# MSP432.net
KiCad netlist of a schematic drawn in Altium Designer
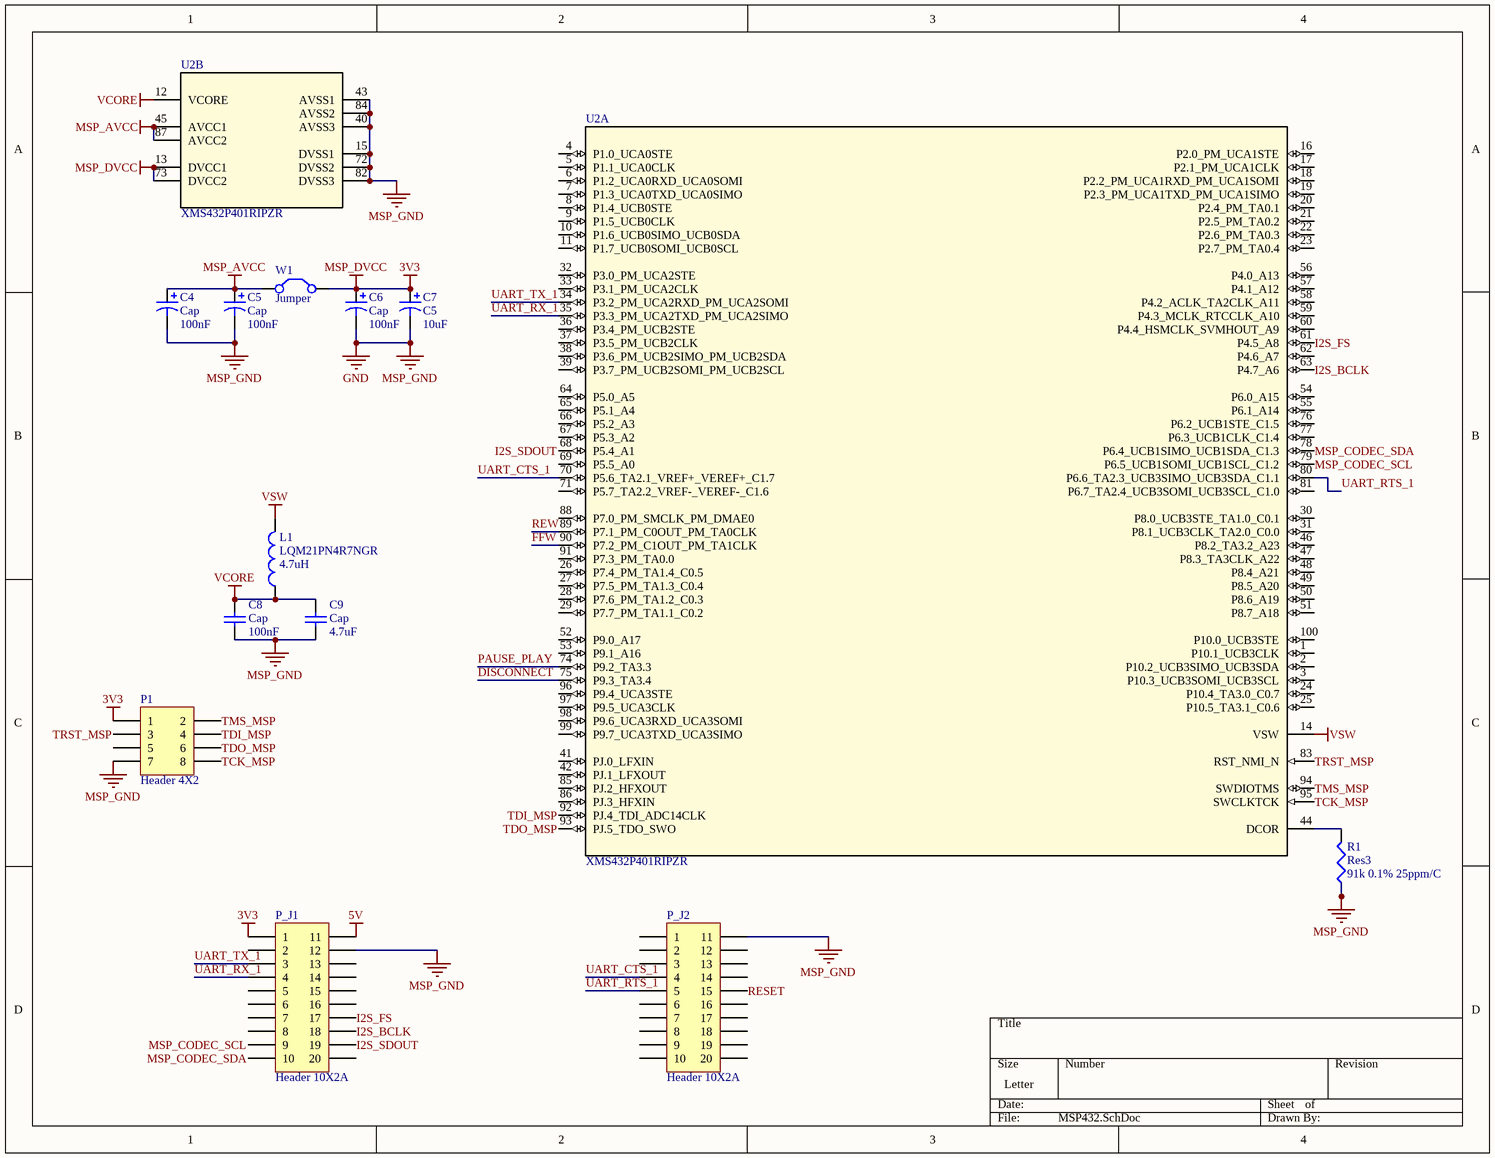
[diagram p0: MSP432.SchDoc]

(export (version "E")
  (design (tool "Eeschema 10.0.6"))
  (components
    (comp (ref "C4")
      (value "Cap")
      (footprint "C0805")
      (description "Polarized Capacitor (Surface Mount)")
      (fields (field (name "ALTIUM_VALUE") "100nF") (field (name "PUBLISHER") "Altium Limited"))
      (libsource (lib "Miscellaneous Devices") (part "Cap Pol3"))
    )
    (comp (ref "C5")
      (value "Cap")
      (footprint "C0805")
      (description "Polarized Capacitor (Surface Mount)")
      (fields (field (name "ALTIUM_VALUE") "100nF") (field (name "PUBLISHER") "Altium Limited"))
      (libsource (lib "Miscellaneous Devices") (part "Cap Pol3"))
    )
    (comp (ref "C6")
      (value "Cap")
      (footprint "C0805")
      (description "Polarized Capacitor (Surface Mount)")
      (fields (field (name "ALTIUM_VALUE") "100nF") (field (name "PUBLISHER") "Altium Limited"))
      (libsource (lib "Miscellaneous Devices") (part "Cap Pol3"))
    )
    (comp (ref "C7")
      (value "C5")
      (footprint "C0805")
      (description "Polarized Capacitor (Surface Mount)")
      (fields (field (name "ALTIUM_VALUE") "10uF") (field (name "PUBLISHER") "Altium Limited"))
      (libsource (lib "Miscellaneous Devices") (part "Cap Pol3"))
    )
    (comp (ref "C8")
      (value "Cap")
      (footprint "C0805")
      (description "Capacitor (Semiconductor SIM Model)")
      (fields (field (name "ALTIUM_VALUE") "100nF") (field (name "PUBLISHER") "Altium Limited"))
      (libsource (lib "Miscellaneous Devices") (part "Cap Semi"))
    )
    (comp (ref "C9")
      (value "Cap")
      (footprint "C0805")
      (description "Capacitor (Semiconductor SIM Model)")
      (fields (field (name "ALTIUM_VALUE") "4.7uF") (field (name "PUBLISHER") "Altium Limited"))
      (libsource (lib "Miscellaneous Devices") (part "Cap Semi"))
    )
    (comp (ref "L1")
      (value "LQM21PN4R7NGR")
      (footprint "6-0805_N")
      (description "Inductor")
      (fields (field (name "ALTIUM_VALUE") "4.7uH") (field (name "PUBLISHER") "Altium Limited"))
      (libsource (lib "Miscellaneous Devices") (part "Inductor"))
    )
    (comp (ref "P1")
      (value "Header 4X2")
      (footprint "HDR2X4")
      (description "Header, 4-Pin, Dual row")
      (fields (field (name "PUBLISHER") "Altium Limited"))
      (libsource (lib "Miscellaneous Connectors") (part "Header 4X2"))
    )
    (comp (ref "P_J1")
      (value "Header 10X2A")
      (footprint "HDR2X10_CEN")
      (description "Header, 10-Pin, Dual row")
      (fields (field (name "PUBLISHER") "Altium Limited"))
      (libsource (lib "Miscellaneous Connectors") (part "Header 10X2A"))
    )
    (comp (ref "P_J2")
      (value "Header 10X2A")
      (footprint "HDR2X10_CEN")
      (description "Header, 10-Pin, Dual row")
      (fields (field (name "PUBLISHER") "Altium Limited"))
      (libsource (lib "Miscellaneous Connectors") (part "Header 10X2A"))
    )
    (comp (ref "R1")
      (value "Res3")
      (footprint "14-1210")
      (description "Resistor")
      (fields (field (name "ALTIUM_VALUE") "91k 0.1% 25ppm/C") (field (name "PUBLISHER") "Altium Limited"))
      (libsource (lib "Miscellaneous Devices") (part "Res3"))
    )
    (comp (ref "U2")
      (value "XMS432P401RIPZR")
      (footprint "PZ0100A_N")
      (description "Imported")
      (fields (field (name "MANUFACTURER") "Texas Instruments"))
      (libsource (lib "XMS432P401R") (part "XMS432P401RIPZR"))
    )
    (comp (ref "W1")
      (value "Jumper")
      (footprint "RAD-0.2")
      (description "Jumper Wire")
      (fields (field (name "PUBLISHER") "Altium Limited"))
      (libsource (lib "Miscellaneous Devices") (part "Jumper"))
    )
  )
  (nets
    (net (code "1") (name "/DISCONNECT") (class "Default")
      (node (ref "U2") (pin "75") (pinfunction "P9.3_TA3.4_75") (pintype "bidirectional"))
    )
    (net (code "2") (name "/FFW") (class "Default")
      (node (ref "U2") (pin "90") (pinfunction "P7.2_PM_C1OUT_PM_TA1CLK_90") (pintype "bidirectional"))
    )
    (net (code "3") (name "/I2S_BCLK") (class "Default")
      (node (ref "P_J1") (pin "18") (pinfunction "18_18") (pintype "passive"))
      (node (ref "U2") (pin "63") (pinfunction "P4.7_A6_63") (pintype "bidirectional"))
    )
    (net (code "4") (name "/I2S_FS") (class "Default")
      (node (ref "P_J1") (pin "17") (pinfunction "17_17") (pintype "passive"))
      (node (ref "U2") (pin "61") (pinfunction "P4.5_A8_61") (pintype "bidirectional"))
    )
    (net (code "5") (name "/I2S_SDOUT") (class "Default")
      (node (ref "P_J1") (pin "19") (pinfunction "19_19") (pintype "passive"))
      (node (ref "U2") (pin "68") (pinfunction "P5.4_A1_68") (pintype "bidirectional"))
    )
    (net (code "6") (name "/MSP_CODEC_SCL") (class "Default")
      (node (ref "P_J1") (pin "9") (pinfunction "9_9") (pintype "passive"))
      (node (ref "U2") (pin "79") (pinfunction "P6.5_UCB1SOMI_UCB1SCL_C1.2_79") (pintype "bidirectional"))
    )
    (net (code "7") (name "/MSP_CODEC_SDA") (class "Default")
      (node (ref "P_J1") (pin "10") (pinfunction "10_10") (pintype "passive"))
      (node (ref "U2") (pin "78") (pinfunction "P6.4_UCB1SIMO_UCB1SDA_C1.3_78") (pintype "bidirectional"))
    )
    (net (code "8") (name "/PAUSE_PLAY") (class "Default")
      (node (ref "U2") (pin "74") (pinfunction "P9.2_TA3.3_74") (pintype "bidirectional"))
    )
    (net (code "9") (name "/RESET") (class "Default")
      (node (ref "P_J2") (pin "15") (pinfunction "15_15") (pintype "passive"))
    )
    (net (code "10") (name "/REW") (class "Default")
      (node (ref "U2") (pin "89") (pinfunction "P7.1_PM_C0OUT_PM_TA0CLK_89") (pintype "bidirectional"))
    )
    (net (code "11") (name "/TCK_MSP") (class "Default")
      (node (ref "P1") (pin "8") (pinfunction "8_8") (pintype "passive"))
      (node (ref "U2") (pin "95") (pinfunction "SWCLKTCK_95") (pintype "input"))
    )
    (net (code "12") (name "/TDI_MSP") (class "Default")
      (node (ref "P1") (pin "4") (pinfunction "4_4") (pintype "passive"))
      (node (ref "U2") (pin "92") (pinfunction "PJ.4_TDI_ADC14CLK_92") (pintype "bidirectional"))
    )
    (net (code "13") (name "/TDO_MSP") (class "Default")
      (node (ref "P1") (pin "6") (pinfunction "6_6") (pintype "passive"))
      (node (ref "U2") (pin "93") (pinfunction "PJ.5_TDO_SWO_93") (pintype "bidirectional"))
    )
    (net (code "14") (name "/TMS_MSP") (class "Default")
      (node (ref "P1") (pin "2") (pinfunction "2_2") (pintype "passive"))
      (node (ref "U2") (pin "94") (pinfunction "SWDIOTMS_94") (pintype "bidirectional"))
    )
    (net (code "15") (name "/TRST_MSP") (class "Default")
      (node (ref "P1") (pin "3") (pinfunction "3_3") (pintype "passive"))
      (node (ref "U2") (pin "83") (pinfunction "RST_NMI_N_83") (pintype "input"))
    )
    (net (code "16") (name "/UART_CTS_1") (class "Default")
      (node (ref "P_J2") (pin "4") (pinfunction "4_4") (pintype "passive"))
      (node (ref "U2") (pin "70") (pinfunction "P5.6_TA2.1_VREF+_VEREF+_C1.7_70") (pintype "bidirectional"))
    )
    (net (code "17") (name "/UART_RTS_1") (class "Default")
      (node (ref "P_J2") (pin "5") (pinfunction "5_5") (pintype "passive"))
      (node (ref "U2") (pin "80") (pinfunction "P6.6_TA2.3_UCB3SIMO_UCB3SDA_C1.1_80") (pintype "bidirectional"))
    )
    (net (code "18") (name "/UART_RX_1") (class "Default")
      (node (ref "P_J1") (pin "4") (pinfunction "4_4") (pintype "passive"))
      (node (ref "U2") (pin "35") (pinfunction "P3.3_PM_UCA2TXD_PM_UCA2SIMO_35") (pintype "bidirectional"))
    )
    (net (code "19") (name "/UART_TX_1") (class "Default")
      (node (ref "P_J1") (pin "3") (pinfunction "3_3") (pintype "passive"))
      (node (ref "U2") (pin "34") (pinfunction "P3.2_PM_UCA2RXD_PM_UCA2SOMI_34") (pintype "bidirectional"))
    )
    (net (code "20") (name "3V3") (class "Default")
      (node (ref "C6") (pin "1") (pinfunction "1_1") (pintype "passive"))
      (node (ref "C7") (pin "1") (pinfunction "1_1") (pintype "passive"))
      (node (ref "P1") (pin "1") (pinfunction "1_1") (pintype "passive"))
      (node (ref "P_J1") (pin "1") (pinfunction "1_1") (pintype "passive"))
      (node (ref "U2") (pin "13") (pinfunction "DVCC1_13") (pintype "power_in"))
      (node (ref "U2") (pin "73") (pinfunction "DVCC2_73") (pintype "power_in"))
      (node (ref "W1") (pin "2") (pinfunction "C2_2") (pintype "passive"))
    )
    (net (code "21") (name "5V") (class "Default")
      (node (ref "P_J1") (pin "11") (pinfunction "11_11") (pintype "passive"))
    )
    (net (code "22") (name "GND") (class "Default")
      (node (ref "C4") (pin "2") (pinfunction "2_2") (pintype "passive"))
      (node (ref "C5") (pin "2") (pinfunction "2_2") (pintype "passive"))
      (node (ref "C6") (pin "2") (pinfunction "2_2") (pintype "passive"))
      (node (ref "C7") (pin "2") (pinfunction "2_2") (pintype "passive"))
      (node (ref "C8") (pin "1") (pinfunction "1_1") (pintype "passive"))
      (node (ref "C9") (pin "2") (pinfunction "2_2") (pintype "passive"))
      (node (ref "P1") (pin "7") (pinfunction "7_7") (pintype "passive"))
      (node (ref "P_J1") (pin "12") (pinfunction "12_12") (pintype "passive"))
      (node (ref "P_J2") (pin "11") (pinfunction "11_11") (pintype "passive"))
      (node (ref "R1") (pin "1") (pinfunction "1_1") (pintype "passive"))
      (node (ref "U2") (pin "15") (pinfunction "DVSS1_15") (pintype "power_in"))
      (node (ref "U2") (pin "40") (pinfunction "AVSS3_40") (pintype "power_in"))
      (node (ref "U2") (pin "43") (pinfunction "AVSS1_43") (pintype "power_in"))
      (node (ref "U2") (pin "72") (pinfunction "DVSS2_72") (pintype "power_in"))
      (node (ref "U2") (pin "82") (pinfunction "DVSS3_82") (pintype "power_in"))
      (node (ref "U2") (pin "84") (pinfunction "AVSS2_84") (pintype "power_in"))
    )
    (net (code "23") (name "MSP_AVCC") (class "Default")
      (node (ref "C4") (pin "1") (pinfunction "1_1") (pintype "passive"))
      (node (ref "C5") (pin "1") (pinfunction "1_1") (pintype "passive"))
      (node (ref "U2") (pin "45") (pinfunction "AVCC1_45") (pintype "power_in"))
      (node (ref "U2") (pin "87") (pinfunction "AVCC2_87") (pintype "power_in"))
      (node (ref "W1") (pin "1") (pinfunction "C1_1") (pintype "passive"))
    )
    (net (code "24") (name "Net-(U2A-DCOR)") (class "Default")
      (node (ref "R1") (pin "2") (pinfunction "2_2") (pintype "passive"))
      (node (ref "U2") (pin "44") (pinfunction "DCOR_44") (pintype "passive"))
    )
    (net (code "25") (name "VCORE") (class "Default")
      (node (ref "C8") (pin "2") (pinfunction "2_2") (pintype "passive"))
      (node (ref "C9") (pin "1") (pinfunction "1_1") (pintype "passive"))
      (node (ref "L1") (pin "1") (pinfunction "1_1") (pintype "passive"))
      (node (ref "U2") (pin "12") (pinfunction "VCORE_12") (pintype "power_in"))
    )
    (net (code "26") (name "VSW") (class "Default")
      (node (ref "L1") (pin "2") (pinfunction "2_2") (pintype "passive"))
      (node (ref "U2") (pin "14") (pinfunction "VSW_14") (pintype "passive"))
    )
    (net (code "27") (name "unconnected-(P1-Pad5)") (class "Default")
      (node (ref "P1") (pin "5") (pinfunction "5_5") (pintype "passive"))
    )
    (net (code "28") (name "unconnected-(P_J1-Pad2)") (class "Default")
      (node (ref "P_J1") (pin "2") (pinfunction "2_2") (pintype "passive"))
    )
    (net (code "29") (name "unconnected-(P_J1-Pad5)") (class "Default")
      (node (ref "P_J1") (pin "5") (pinfunction "5_5") (pintype "passive"))
    )
    (net (code "30") (name "unconnected-(P_J1-Pad6)") (class "Default")
      (node (ref "P_J1") (pin "6") (pinfunction "6_6") (pintype "passive"))
    )
    (net (code "31") (name "unconnected-(P_J1-Pad7)") (class "Default")
      (node (ref "P_J1") (pin "7") (pinfunction "7_7") (pintype "passive"))
    )
    (net (code "32") (name "unconnected-(P_J1-Pad8)") (class "Default")
      (node (ref "P_J1") (pin "8") (pinfunction "8_8") (pintype "passive"))
    )
    (net (code "33") (name "unconnected-(P_J1-Pad13)") (class "Default")
      (node (ref "P_J1") (pin "13") (pinfunction "13_13") (pintype "passive"))
    )
    (net (code "34") (name "unconnected-(P_J1-Pad14)") (class "Default")
      (node (ref "P_J1") (pin "14") (pinfunction "14_14") (pintype "passive"))
    )
    (net (code "35") (name "unconnected-(P_J1-Pad15)") (class "Default")
      (node (ref "P_J1") (pin "15") (pinfunction "15_15") (pintype "passive"))
    )
    (net (code "36") (name "unconnected-(P_J1-Pad16)") (class "Default")
      (node (ref "P_J1") (pin "16") (pinfunction "16_16") (pintype "passive"))
    )
    (net (code "37") (name "unconnected-(P_J1-Pad20)") (class "Default")
      (node (ref "P_J1") (pin "20") (pinfunction "20_20") (pintype "passive"))
    )
    (net (code "38") (name "unconnected-(P_J2-Pad1)") (class "Default")
      (node (ref "P_J2") (pin "1") (pinfunction "1_1") (pintype "passive"))
    )
    (net (code "39") (name "unconnected-(P_J2-Pad2)") (class "Default")
      (node (ref "P_J2") (pin "2") (pinfunction "2_2") (pintype "passive"))
    )
    (net (code "40") (name "unconnected-(P_J2-Pad3)") (class "Default")
      (node (ref "P_J2") (pin "3") (pinfunction "3_3") (pintype "passive"))
    )
    (net (code "41") (name "unconnected-(P_J2-Pad6)") (class "Default")
      (node (ref "P_J2") (pin "6") (pinfunction "6_6") (pintype "passive"))
    )
    (net (code "42") (name "unconnected-(P_J2-Pad7)") (class "Default")
      (node (ref "P_J2") (pin "7") (pinfunction "7_7") (pintype "passive"))
    )
    (net (code "43") (name "unconnected-(P_J2-Pad8)") (class "Default")
      (node (ref "P_J2") (pin "8") (pinfunction "8_8") (pintype "passive"))
    )
    (net (code "44") (name "unconnected-(P_J2-Pad9)") (class "Default")
      (node (ref "P_J2") (pin "9") (pinfunction "9_9") (pintype "passive"))
    )
    (net (code "45") (name "unconnected-(P_J2-Pad10)") (class "Default")
      (node (ref "P_J2") (pin "10") (pinfunction "10_10") (pintype "passive"))
    )
    (net (code "46") (name "unconnected-(P_J2-Pad12)") (class "Default")
      (node (ref "P_J2") (pin "12") (pinfunction "12_12") (pintype "passive"))
    )
    (net (code "47") (name "unconnected-(P_J2-Pad13)") (class "Default")
      (node (ref "P_J2") (pin "13") (pinfunction "13_13") (pintype "passive"))
    )
    (net (code "48") (name "unconnected-(P_J2-Pad14)") (class "Default")
      (node (ref "P_J2") (pin "14") (pinfunction "14_14") (pintype "passive"))
    )
    (net (code "49") (name "unconnected-(P_J2-Pad16)") (class "Default")
      (node (ref "P_J2") (pin "16") (pinfunction "16_16") (pintype "passive"))
    )
    (net (code "50") (name "unconnected-(P_J2-Pad17)") (class "Default")
      (node (ref "P_J2") (pin "17") (pinfunction "17_17") (pintype "passive"))
    )
    (net (code "51") (name "unconnected-(P_J2-Pad18)") (class "Default")
      (node (ref "P_J2") (pin "18") (pinfunction "18_18") (pintype "passive"))
    )
    (net (code "52") (name "unconnected-(P_J2-Pad19)") (class "Default")
      (node (ref "P_J2") (pin "19") (pinfunction "19_19") (pintype "passive"))
    )
    (net (code "53") (name "unconnected-(P_J2-Pad20)") (class "Default")
      (node (ref "P_J2") (pin "20") (pinfunction "20_20") (pintype "passive"))
    )
    (net (code "54") (name "unconnected-(U2A-P1.0_UCA0STE-Pad4)") (class "Default")
      (node (ref "U2") (pin "4") (pinfunction "P1.0_UCA0STE_4") (pintype "bidirectional"))
    )
    (net (code "55") (name "unconnected-(U2A-P1.1_UCA0CLK-Pad5)") (class "Default")
      (node (ref "U2") (pin "5") (pinfunction "P1.1_UCA0CLK_5") (pintype "bidirectional"))
    )
    (net (code "56") (name "unconnected-(U2A-P1.2_UCA0RXD_UCA0SOMI-Pad6)") (class "Default")
      (node (ref "U2") (pin "6") (pinfunction "P1.2_UCA0RXD_UCA0SOMI_6") (pintype "bidirectional"))
    )
    (net (code "57") (name "unconnected-(U2A-P1.3_UCA0TXD_UCA0SIMO-Pad7)") (class "Default")
      (node (ref "U2") (pin "7") (pinfunction "P1.3_UCA0TXD_UCA0SIMO_7") (pintype "bidirectional"))
    )
    (net (code "58") (name "unconnected-(U2A-P1.4_UCB0STE-Pad8)") (class "Default")
      (node (ref "U2") (pin "8") (pinfunction "P1.4_UCB0STE_8") (pintype "bidirectional"))
    )
    (net (code "59") (name "unconnected-(U2A-P1.5_UCB0CLK-Pad9)") (class "Default")
      (node (ref "U2") (pin "9") (pinfunction "P1.5_UCB0CLK_9") (pintype "bidirectional"))
    )
    (net (code "60") (name "unconnected-(U2A-P1.6_UCB0SIMO_UCB0SDA-Pad10)") (class "Default")
      (node (ref "U2") (pin "10") (pinfunction "P1.6_UCB0SIMO_UCB0SDA_10") (pintype "bidirectional"))
    )
    (net (code "61") (name "unconnected-(U2A-P1.7_UCB0SOMI_UCB0SCL-Pad11)") (class "Default")
      (node (ref "U2") (pin "11") (pinfunction "P1.7_UCB0SOMI_UCB0SCL_11") (pintype "bidirectional"))
    )
    (net (code "62") (name "unconnected-(U2A-P2.0_PM_UCA1STE-Pad16)") (class "Default")
      (node (ref "U2") (pin "16") (pinfunction "P2.0_PM_UCA1STE_16") (pintype "bidirectional"))
    )
    (net (code "63") (name "unconnected-(U2A-P2.1_PM_UCA1CLK-Pad17)") (class "Default")
      (node (ref "U2") (pin "17") (pinfunction "P2.1_PM_UCA1CLK_17") (pintype "bidirectional"))
    )
    (net (code "64") (name "unconnected-(U2A-P2.2_PM_UCA1RXD_PM_UCA1SOMI-Pad18)") (class "Default")
      (node (ref "U2") (pin "18") (pinfunction "P2.2_PM_UCA1RXD_PM_UCA1SOMI_18") (pintype "bidirectional"))
    )
    (net (code "65") (name "unconnected-(U2A-P2.3_PM_UCA1TXD_PM_UCA1SIMO-Pad19)") (class "Default")
      (node (ref "U2") (pin "19") (pinfunction "P2.3_PM_UCA1TXD_PM_UCA1SIMO_19") (pintype "bidirectional"))
    )
    (net (code "66") (name "unconnected-(U2A-P2.4_PM_TA0.1-Pad20)") (class "Default")
      (node (ref "U2") (pin "20") (pinfunction "P2.4_PM_TA0.1_20") (pintype "bidirectional"))
    )
    (net (code "67") (name "unconnected-(U2A-P2.5_PM_TA0.2-Pad21)") (class "Default")
      (node (ref "U2") (pin "21") (pinfunction "P2.5_PM_TA0.2_21") (pintype "bidirectional"))
    )
    (net (code "68") (name "unconnected-(U2A-P2.6_PM_TA0.3-Pad22)") (class "Default")
      (node (ref "U2") (pin "22") (pinfunction "P2.6_PM_TA0.3_22") (pintype "bidirectional"))
    )
    (net (code "69") (name "unconnected-(U2A-P2.7_PM_TA0.4-Pad23)") (class "Default")
      (node (ref "U2") (pin "23") (pinfunction "P2.7_PM_TA0.4_23") (pintype "bidirectional"))
    )
    (net (code "70") (name "unconnected-(U2A-P3.0_PM_UCA2STE-Pad32)") (class "Default")
      (node (ref "U2") (pin "32") (pinfunction "P3.0_PM_UCA2STE_32") (pintype "bidirectional"))
    )
    (net (code "71") (name "unconnected-(U2A-P3.1_PM_UCA2CLK-Pad33)") (class "Default")
      (node (ref "U2") (pin "33") (pinfunction "P3.1_PM_UCA2CLK_33") (pintype "bidirectional"))
    )
    (net (code "72") (name "unconnected-(U2A-P3.4_PM_UCB2STE-Pad36)") (class "Default")
      (node (ref "U2") (pin "36") (pinfunction "P3.4_PM_UCB2STE_36") (pintype "bidirectional"))
    )
    (net (code "73") (name "unconnected-(U2A-P3.5_PM_UCB2CLK-Pad37)") (class "Default")
      (node (ref "U2") (pin "37") (pinfunction "P3.5_PM_UCB2CLK_37") (pintype "bidirectional"))
    )
    (net (code "74") (name "unconnected-(U2A-P3.6_PM_UCB2SIMO_PM_UCB2SDA-Pad38)") (class "Default")
      (node (ref "U2") (pin "38") (pinfunction "P3.6_PM_UCB2SIMO_PM_UCB2SDA_38") (pintype "bidirectional"))
    )
    (net (code "75") (name "unconnected-(U2A-P3.7_PM_UCB2SOMI_PM_UCB2SCL-Pad39)") (class "Default")
      (node (ref "U2") (pin "39") (pinfunction "P3.7_PM_UCB2SOMI_PM_UCB2SCL_39") (pintype "bidirectional"))
    )
    (net (code "76") (name "unconnected-(U2A-P4.0_A13-Pad56)") (class "Default")
      (node (ref "U2") (pin "56") (pinfunction "P4.0_A13_56") (pintype "bidirectional"))
    )
    (net (code "77") (name "unconnected-(U2A-P4.1_A12-Pad57)") (class "Default")
      (node (ref "U2") (pin "57") (pinfunction "P4.1_A12_57") (pintype "bidirectional"))
    )
    (net (code "78") (name "unconnected-(U2A-P4.2_ACLK_TA2CLK_A11-Pad58)") (class "Default")
      (node (ref "U2") (pin "58") (pinfunction "P4.2_ACLK_TA2CLK_A11_58") (pintype "bidirectional"))
    )
    (net (code "79") (name "unconnected-(U2A-P4.3_MCLK_RTCCLK_A10-Pad59)") (class "Default")
      (node (ref "U2") (pin "59") (pinfunction "P4.3_MCLK_RTCCLK_A10_59") (pintype "bidirectional"))
    )
    (net (code "80") (name "unconnected-(U2A-P4.4_HSMCLK_SVMHOUT_A9-Pad60)") (class "Default")
      (node (ref "U2") (pin "60") (pinfunction "P4.4_HSMCLK_SVMHOUT_A9_60") (pintype "bidirectional"))
    )
    (net (code "81") (name "unconnected-(U2A-P4.6_A7-Pad62)") (class "Default")
      (node (ref "U2") (pin "62") (pinfunction "P4.6_A7_62") (pintype "bidirectional"))
    )
    (net (code "82") (name "unconnected-(U2A-P5.0_A5-Pad64)") (class "Default")
      (node (ref "U2") (pin "64") (pinfunction "P5.0_A5_64") (pintype "bidirectional"))
    )
    (net (code "83") (name "unconnected-(U2A-P5.1_A4-Pad65)") (class "Default")
      (node (ref "U2") (pin "65") (pinfunction "P5.1_A4_65") (pintype "bidirectional"))
    )
    (net (code "84") (name "unconnected-(U2A-P5.2_A3-Pad66)") (class "Default")
      (node (ref "U2") (pin "66") (pinfunction "P5.2_A3_66") (pintype "bidirectional"))
    )
    (net (code "85") (name "unconnected-(U2A-P5.3_A2-Pad67)") (class "Default")
      (node (ref "U2") (pin "67") (pinfunction "P5.3_A2_67") (pintype "bidirectional"))
    )
    (net (code "86") (name "unconnected-(U2A-P5.5_A0-Pad69)") (class "Default")
      (node (ref "U2") (pin "69") (pinfunction "P5.5_A0_69") (pintype "bidirectional"))
    )
    (net (code "87") (name "unconnected-(U2A-P5.7_TA2.2_VREF-_VEREF-_C1.6-Pad71)") (class "Default")
      (node (ref "U2") (pin "71") (pinfunction "P5.7_TA2.2_VREF-_VEREF-_C1.6_71") (pintype "bidirectional"))
    )
    (net (code "88") (name "unconnected-(U2A-P6.0_A15-Pad54)") (class "Default")
      (node (ref "U2") (pin "54") (pinfunction "P6.0_A15_54") (pintype "bidirectional"))
    )
    (net (code "89") (name "unconnected-(U2A-P6.1_A14-Pad55)") (class "Default")
      (node (ref "U2") (pin "55") (pinfunction "P6.1_A14_55") (pintype "bidirectional"))
    )
    (net (code "90") (name "unconnected-(U2A-P6.2_UCB1STE_C1.5-Pad76)") (class "Default")
      (node (ref "U2") (pin "76") (pinfunction "P6.2_UCB1STE_C1.5_76") (pintype "bidirectional"))
    )
    (net (code "91") (name "unconnected-(U2A-P6.3_UCB1CLK_C1.4-Pad77)") (class "Default")
      (node (ref "U2") (pin "77") (pinfunction "P6.3_UCB1CLK_C1.4_77") (pintype "bidirectional"))
    )
    (net (code "92") (name "unconnected-(U2A-P6.7_TA2.4_UCB3SOMI_UCB3SCL_C1.0-Pad81)") (class "Default")
      (node (ref "U2") (pin "81") (pinfunction "P6.7_TA2.4_UCB3SOMI_UCB3SCL_C1.0_81") (pintype "bidirectional"))
    )
    (net (code "93") (name "unconnected-(U2A-P7.0_PM_SMCLK_PM_DMAE0-Pad88)") (class "Default")
      (node (ref "U2") (pin "88") (pinfunction "P7.0_PM_SMCLK_PM_DMAE0_88") (pintype "bidirectional"))
    )
    (net (code "94") (name "unconnected-(U2A-P7.3_PM_TA0.0-Pad91)") (class "Default")
      (node (ref "U2") (pin "91") (pinfunction "P7.3_PM_TA0.0_91") (pintype "bidirectional"))
    )
    (net (code "95") (name "unconnected-(U2A-P7.4_PM_TA1.4_C0.5-Pad26)") (class "Default")
      (node (ref "U2") (pin "26") (pinfunction "P7.4_PM_TA1.4_C0.5_26") (pintype "bidirectional"))
    )
    (net (code "96") (name "unconnected-(U2A-P7.5_PM_TA1.3_C0.4-Pad27)") (class "Default")
      (node (ref "U2") (pin "27") (pinfunction "P7.5_PM_TA1.3_C0.4_27") (pintype "bidirectional"))
    )
    (net (code "97") (name "unconnected-(U2A-P7.6_PM_TA1.2_C0.3-Pad28)") (class "Default")
      (node (ref "U2") (pin "28") (pinfunction "P7.6_PM_TA1.2_C0.3_28") (pintype "bidirectional"))
    )
    (net (code "98") (name "unconnected-(U2A-P7.7_PM_TA1.1_C0.2-Pad29)") (class "Default")
      (node (ref "U2") (pin "29") (pinfunction "P7.7_PM_TA1.1_C0.2_29") (pintype "bidirectional"))
    )
    (net (code "99") (name "unconnected-(U2A-P8.0_UCB3STE_TA1.0_C0.1-Pad30)") (class "Default")
      (node (ref "U2") (pin "30") (pinfunction "P8.0_UCB3STE_TA1.0_C0.1_30") (pintype "bidirectional"))
    )
    (net (code "100") (name "unconnected-(U2A-P8.1_UCB3CLK_TA2.0_C0.0-Pad31)") (class "Default")
      (node (ref "U2") (pin "31") (pinfunction "P8.1_UCB3CLK_TA2.0_C0.0_31") (pintype "bidirectional"))
    )
    (net (code "101") (name "unconnected-(U2A-P8.2_TA3.2_A23-Pad46)") (class "Default")
      (node (ref "U2") (pin "46") (pinfunction "P8.2_TA3.2_A23_46") (pintype "bidirectional"))
    )
    (net (code "102") (name "unconnected-(U2A-P8.3_TA3CLK_A22-Pad47)") (class "Default")
      (node (ref "U2") (pin "47") (pinfunction "P8.3_TA3CLK_A22_47") (pintype "bidirectional"))
    )
    (net (code "103") (name "unconnected-(U2A-P8.4_A21-Pad48)") (class "Default")
      (node (ref "U2") (pin "48") (pinfunction "P8.4_A21_48") (pintype "bidirectional"))
    )
    (net (code "104") (name "unconnected-(U2A-P8.5_A20-Pad49)") (class "Default")
      (node (ref "U2") (pin "49") (pinfunction "P8.5_A20_49") (pintype "bidirectional"))
    )
    (net (code "105") (name "unconnected-(U2A-P8.6_A19-Pad50)") (class "Default")
      (node (ref "U2") (pin "50") (pinfunction "P8.6_A19_50") (pintype "bidirectional"))
    )
    (net (code "106") (name "unconnected-(U2A-P8.7_A18-Pad51)") (class "Default")
      (node (ref "U2") (pin "51") (pinfunction "P8.7_A18_51") (pintype "bidirectional"))
    )
    (net (code "107") (name "unconnected-(U2A-P9.0_A17-Pad52)") (class "Default")
      (node (ref "U2") (pin "52") (pinfunction "P9.0_A17_52") (pintype "bidirectional"))
    )
    (net (code "108") (name "unconnected-(U2A-P9.1_A16-Pad53)") (class "Default")
      (node (ref "U2") (pin "53") (pinfunction "P9.1_A16_53") (pintype "bidirectional"))
    )
    (net (code "109") (name "unconnected-(U2A-P9.4_UCA3STE-Pad96)") (class "Default")
      (node (ref "U2") (pin "96") (pinfunction "P9.4_UCA3STE_96") (pintype "bidirectional"))
    )
    (net (code "110") (name "unconnected-(U2A-P9.5_UCA3CLK-Pad97)") (class "Default")
      (node (ref "U2") (pin "97") (pinfunction "P9.5_UCA3CLK_97") (pintype "bidirectional"))
    )
    (net (code "111") (name "unconnected-(U2A-P9.6_UCA3RXD_UCA3SOMI-Pad98)") (class "Default")
      (node (ref "U2") (pin "98") (pinfunction "P9.6_UCA3RXD_UCA3SOMI_98") (pintype "bidirectional"))
    )
    (net (code "112") (name "unconnected-(U2A-P9.7_UCA3TXD_UCA3SIMO-Pad99)") (class "Default")
      (node (ref "U2") (pin "99") (pinfunction "P9.7_UCA3TXD_UCA3SIMO_99") (pintype "bidirectional"))
    )
    (net (code "113") (name "unconnected-(U2A-P10.0_UCB3STE-Pad100)") (class "Default")
      (node (ref "U2") (pin "100") (pinfunction "P10.0_UCB3STE_100") (pintype "bidirectional"))
    )
    (net (code "114") (name "unconnected-(U2A-P10.1_UCB3CLK-Pad1)") (class "Default")
      (node (ref "U2") (pin "1") (pinfunction "P10.1_UCB3CLK_1") (pintype "bidirectional"))
    )
    (net (code "115") (name "unconnected-(U2A-P10.2_UCB3SIMO_UCB3SDA-Pad2)") (class "Default")
      (node (ref "U2") (pin "2") (pinfunction "P10.2_UCB3SIMO_UCB3SDA_2") (pintype "bidirectional"))
    )
    (net (code "116") (name "unconnected-(U2A-P10.3_UCB3SOMI_UCB3SCL-Pad3)") (class "Default")
      (node (ref "U2") (pin "3") (pinfunction "P10.3_UCB3SOMI_UCB3SCL_3") (pintype "bidirectional"))
    )
    (net (code "117") (name "unconnected-(U2A-P10.4_TA3.0_C0.7-Pad24)") (class "Default")
      (node (ref "U2") (pin "24") (pinfunction "P10.4_TA3.0_C0.7_24") (pintype "bidirectional"))
    )
    (net (code "118") (name "unconnected-(U2A-P10.5_TA3.1_C0.6-Pad25)") (class "Default")
      (node (ref "U2") (pin "25") (pinfunction "P10.5_TA3.1_C0.6_25") (pintype "bidirectional"))
    )
    (net (code "119") (name "unconnected-(U2A-PJ.0_LFXIN-Pad41)") (class "Default")
      (node (ref "U2") (pin "41") (pinfunction "PJ.0_LFXIN_41") (pintype "bidirectional"))
    )
    (net (code "120") (name "unconnected-(U2A-PJ.1_LFXOUT-Pad42)") (class "Default")
      (node (ref "U2") (pin "42") (pinfunction "PJ.1_LFXOUT_42") (pintype "bidirectional"))
    )
    (net (code "121") (name "unconnected-(U2A-PJ.2_HFXOUT-Pad85)") (class "Default")
      (node (ref "U2") (pin "85") (pinfunction "PJ.2_HFXOUT_85") (pintype "bidirectional"))
    )
    (net (code "122") (name "unconnected-(U2A-PJ.3_HFXIN-Pad86)") (class "Default")
      (node (ref "U2") (pin "86") (pinfunction "PJ.3_HFXIN_86") (pintype "bidirectional"))
    )
  )
)
